# rev_B.net
KiCad netlist of a schematic drawn in EAGLE
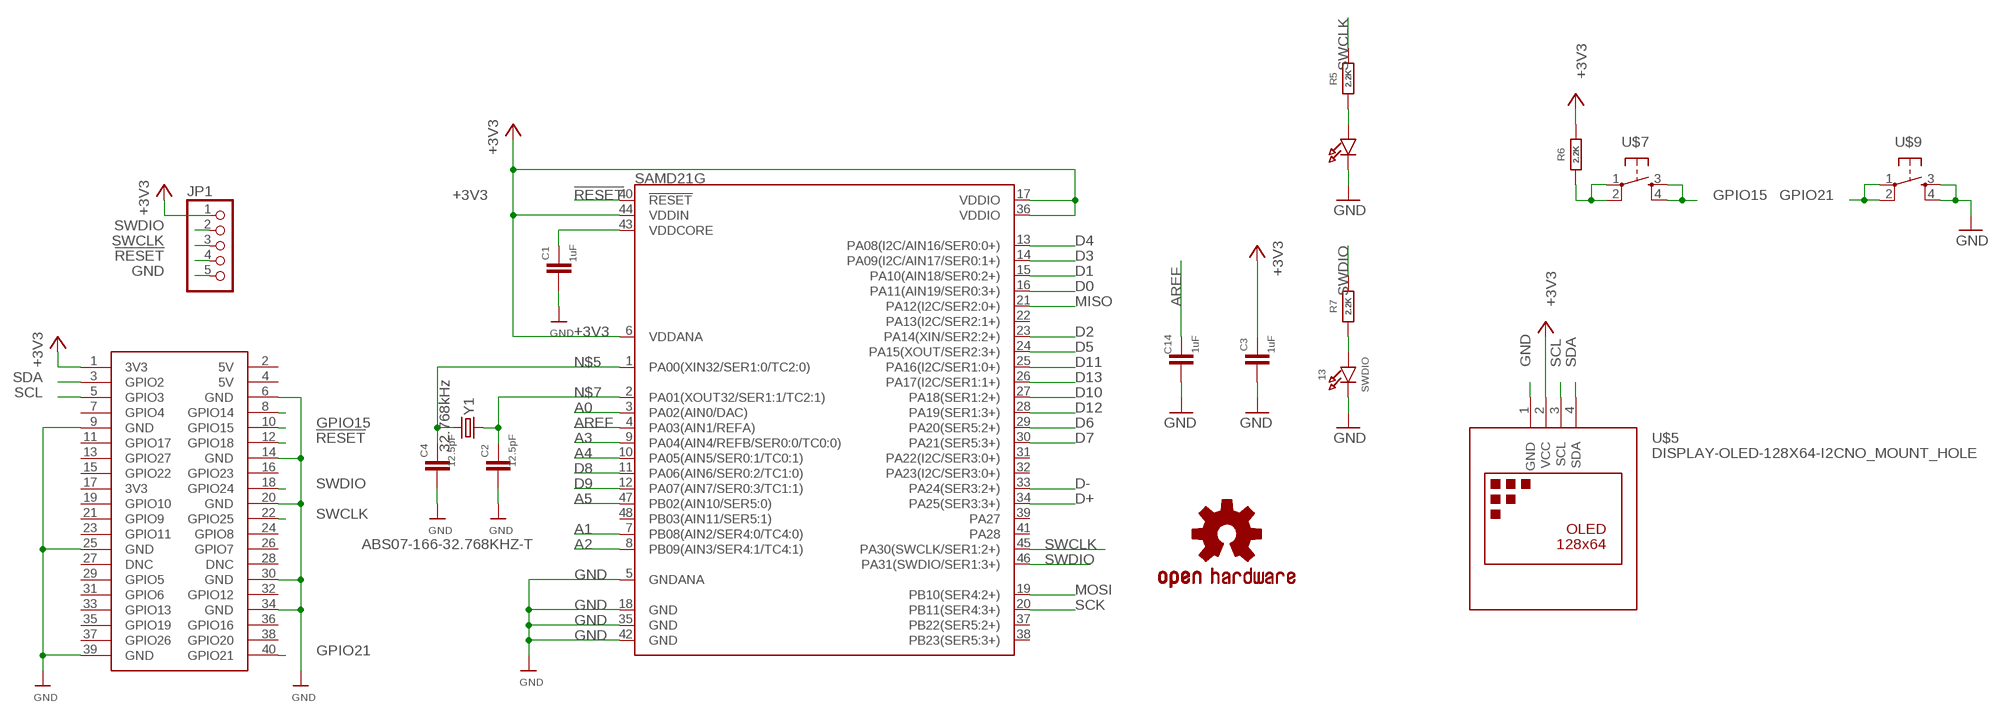
[diagram p0: schematic, sheet 1]

(export (version "E")
  (design (tool "Eeschema 10.0.6"))
  (components
    (comp (ref "5")
      (value "SWCLK")
      (footprint "eagle-import:CHIPLED_0805_NOOUTLINE")
      (libsource (lib "eagle-import") (part "LED0805_NOOUTLINE"))
    )
    (comp (ref "13")
      (value "SWDIO")
      (footprint "eagle-import:CHIPLED_0805_NOOUTLINE")
      (libsource (lib "eagle-import") (part "LED0805_NOOUTLINE"))
    )
    (comp (ref "C1")
      (value "1uF")
      (footprint "eagle-import:C0805")
      (libsource (lib "eagle-import") (part "C-EUC0805"))
    )
    (comp (ref "C2")
      (value "12.5pF")
      (footprint "eagle-import:C0805")
      (libsource (lib "eagle-import") (part "C-EUC0805"))
    )
    (comp (ref "C3")
      (value "1uF")
      (footprint "eagle-import:C0805")
      (libsource (lib "eagle-import") (part "C-EUC0805"))
    )
    (comp (ref "C4")
      (value "12.5pF")
      (footprint "eagle-import:C0805")
      (libsource (lib "eagle-import") (part "C-EUC0805"))
    )
    (comp (ref "C14")
      (value "1uF")
      (footprint "eagle-import:C0805")
      (libsource (lib "eagle-import") (part "C-EUC0805"))
    )
    (comp (ref "JP1")
      (value "PINHD-1X5")
      (footprint "eagle-import:1X05")
      (libsource (lib "eagle-import") (part "PINHD-1X5"))
    )
    (comp (ref "LOGO1")
      (value "OSHW-LOGOS")
      (footprint "eagle-import:OSHW-LOGO-S")
      (libsource (lib "eagle-import") (part "OSHW-LOGOS"))
    )
    (comp (ref "R5")
      (value "2.2K")
      (footprint "eagle-import:R0805")
      (libsource (lib "eagle-import") (part "R-EU_R0805"))
    )
    (comp (ref "R6")
      (value "2.2K")
      (footprint "eagle-import:R0805")
      (libsource (lib "eagle-import") (part "R-EU_R0805"))
    )
    (comp (ref "R7")
      (value "2.2K")
      (footprint "eagle-import:R0805")
      (libsource (lib "eagle-import") (part "R-EU_R0805"))
    )
    (comp (ref "SAMD21G")
      (value "ATSAMD21G-A")
      (footprint "eagle-import:TQFP-48")
      (libsource (lib "eagle-import") (part "ATSAMD21G-A"))
    )
    (comp (ref "U$1")
      (value "RASPBERRY_PI_ZERO")
      (footprint "eagle-import:RASPBERRY_PI_ZERO")
      (libsource (lib "eagle-import") (part "RASPBERRY_PI_ZERO"))
    )
    (comp (ref "U$5")
      (value "DISPLAY-OLED-128X64-I2CNO_MOUNT_HOLE")
      (footprint "eagle-import:DISPLAY-OLED-128X64-I2C")
      (libsource (lib "eagle-import") (part "DISPLAY-OLED-128X64-I2CNO_MOUNT_HOLE"))
    )
    (comp (ref "U$7")
      (value "TACTILE_SWITCH_LONG_THT_")
      (footprint "eagle-import:TACTILE_SWICTH_THT")
      (libsource (lib "eagle-import") (part "TACTILE_SWITCH_LONG_THT_"))
    )
    (comp (ref "U$9")
      (value "TACTILE_SWITCH_LONG_THT_")
      (footprint "eagle-import:TACTILE_SWICTH_THT")
      (libsource (lib "eagle-import") (part "TACTILE_SWITCH_LONG_THT_"))
    )
    (comp (ref "Y1")
      (value "32.768kHz")
      (footprint "eagle-import:CRYSTAL-SMD-3.2X1.5MM")
      (libsource (lib "eagle-import") (part "CRYSTAL3.2X1.5MM"))
    )
  )
  (nets
    (net (code "1") (name "+3V3") (class "Default")
      (node (ref "C3") (pin "1") (pinfunction "1_1") (pintype "passive"))
      (node (ref "JP1") (pin "1") (pinfunction "1_1") (pintype "passive"))
      (node (ref "R6") (pin "1") (pinfunction "1_1") (pintype "passive"))
      (node (ref "SAMD21G") (pin "17") (pinfunction "VDDIO_17") (pintype "bidirectional"))
      (node (ref "SAMD21G") (pin "36") (pinfunction "VDDIO_36") (pintype "bidirectional"))
      (node (ref "SAMD21G") (pin "44") (pinfunction "VDDIN_44") (pintype "bidirectional"))
      (node (ref "SAMD21G") (pin "6") (pinfunction "VDDANA_6") (pintype "bidirectional"))
      (node (ref "U$1") (pin "1") (pinfunction "3V3_1") (pintype "bidirectional"))
      (node (ref "U$5") (pin "2") (pinfunction "VCC_2") (pintype "power_in"))
    )
    (net (code "2") (name "/A0") (class "Default")
      (node (ref "SAMD21G") (pin "3") (pinfunction "PA02(AIN0/DAC)_3") (pintype "bidirectional"))
    )
    (net (code "3") (name "/A1") (class "Default")
      (node (ref "SAMD21G") (pin "7") (pinfunction "PB08(AIN2/SER4:0/TC4:0)_7") (pintype "bidirectional"))
    )
    (net (code "4") (name "/A2") (class "Default")
      (node (ref "SAMD21G") (pin "8") (pinfunction "PB09(AIN3/SER4:1/TC4:1)_8") (pintype "bidirectional"))
    )
    (net (code "5") (name "/A3") (class "Default")
      (node (ref "SAMD21G") (pin "9") (pinfunction "PA04(AIN4/REFB/SER0:0/TC0:0)_9") (pintype "bidirectional"))
    )
    (net (code "6") (name "/A4") (class "Default")
      (node (ref "SAMD21G") (pin "10") (pinfunction "PA05(AIN5/SER0:1/TC0:1)_10") (pintype "bidirectional"))
    )
    (net (code "7") (name "/A5") (class "Default")
      (node (ref "SAMD21G") (pin "47") (pinfunction "PB02(AIN10/SER5:0)_47") (pintype "bidirectional"))
    )
    (net (code "8") (name "/AREF") (class "Default")
      (node (ref "C14") (pin "1") (pinfunction "1_1") (pintype "passive"))
      (node (ref "SAMD21G") (pin "4") (pinfunction "PA03(AIN1/REFA)_4") (pintype "bidirectional"))
    )
    (net (code "9") (name "/D+") (class "Default")
      (node (ref "SAMD21G") (pin "34") (pinfunction "PA25(SER3:3+)_34") (pintype "bidirectional"))
    )
    (net (code "10") (name "/D-") (class "Default")
      (node (ref "SAMD21G") (pin "33") (pinfunction "PA24(SER3:2+)_33") (pintype "bidirectional"))
    )
    (net (code "11") (name "/D0") (class "Default")
      (node (ref "SAMD21G") (pin "16") (pinfunction "PA11(AIN19/SER0:3+)_16") (pintype "bidirectional"))
    )
    (net (code "12") (name "/D1") (class "Default")
      (node (ref "SAMD21G") (pin "15") (pinfunction "PA10(AIN18/SER0:2+)_15") (pintype "bidirectional"))
    )
    (net (code "13") (name "/D2") (class "Default")
      (node (ref "SAMD21G") (pin "23") (pinfunction "PA14(XIN/SER2:2+)_23") (pintype "bidirectional"))
    )
    (net (code "14") (name "/D3") (class "Default")
      (node (ref "SAMD21G") (pin "14") (pinfunction "PA09(I2C/AIN17/SER0:1+)_14") (pintype "bidirectional"))
    )
    (net (code "15") (name "/D4") (class "Default")
      (node (ref "SAMD21G") (pin "13") (pinfunction "PA08(I2C/AIN16/SER0:0+)_13") (pintype "bidirectional"))
    )
    (net (code "16") (name "/D5") (class "Default")
      (node (ref "SAMD21G") (pin "24") (pinfunction "PA15(XOUT/SER2:3+)_24") (pintype "bidirectional"))
    )
    (net (code "17") (name "/D6") (class "Default")
      (node (ref "SAMD21G") (pin "29") (pinfunction "PA20(SER5:2+)_29") (pintype "bidirectional"))
    )
    (net (code "18") (name "/D7") (class "Default")
      (node (ref "SAMD21G") (pin "30") (pinfunction "PA21(SER5:3+)_30") (pintype "bidirectional"))
    )
    (net (code "19") (name "/D8") (class "Default")
      (node (ref "SAMD21G") (pin "11") (pinfunction "PA06(AIN6/SER0:2/TC1:0)_11") (pintype "bidirectional"))
    )
    (net (code "20") (name "/D9") (class "Default")
      (node (ref "SAMD21G") (pin "12") (pinfunction "PA07(AIN7/SER0:3/TC1:1)_12") (pintype "bidirectional"))
    )
    (net (code "21") (name "/D10") (class "Default")
      (node (ref "SAMD21G") (pin "27") (pinfunction "PA18(SER1:2+)_27") (pintype "bidirectional"))
    )
    (net (code "22") (name "/D11") (class "Default")
      (node (ref "SAMD21G") (pin "25") (pinfunction "PA16(I2C/SER1:0+)_25") (pintype "bidirectional"))
    )
    (net (code "23") (name "/D12") (class "Default")
      (node (ref "SAMD21G") (pin "28") (pinfunction "PA19(SER1:3+)_28") (pintype "bidirectional"))
    )
    (net (code "24") (name "/D13") (class "Default")
      (node (ref "SAMD21G") (pin "26") (pinfunction "PA17(I2C/SER1:1+)_26") (pintype "bidirectional"))
    )
    (net (code "25") (name "/GPIO15") (class "Default")
      (node (ref "U$1") (pin "10") (pinfunction "GPIO15_10") (pintype "bidirectional"))
      (node (ref "U$7") (pin "3") (pinfunction "3_3") (pintype "passive"))
      (node (ref "U$7") (pin "4") (pinfunction "4_4") (pintype "passive"))
    )
    (net (code "26") (name "/GPIO21") (class "Default")
      (node (ref "U$1") (pin "40") (pinfunction "GPIO21_40") (pintype "bidirectional"))
      (node (ref "U$9") (pin "1") (pinfunction "1_1") (pintype "passive"))
      (node (ref "U$9") (pin "2") (pinfunction "2_2") (pintype "passive"))
    )
    (net (code "27") (name "/MISO") (class "Default")
      (node (ref "SAMD21G") (pin "21") (pinfunction "PA12(I2C/SER2:0+)_21") (pintype "bidirectional"))
    )
    (net (code "28") (name "/MOSI") (class "Default")
      (node (ref "SAMD21G") (pin "19") (pinfunction "PB10(SER4:2+)_19") (pintype "bidirectional"))
    )
    (net (code "29") (name "/N$5") (class "Default")
      (node (ref "C4") (pin "1") (pinfunction "1_1") (pintype "passive"))
      (node (ref "SAMD21G") (pin "1") (pinfunction "PA00(XIN32/SER1:0/TC2:0)_1") (pintype "bidirectional"))
      (node (ref "Y1") (pin "P$2") (pinfunction "2_P$2") (pintype "passive"))
    )
    (net (code "30") (name "/N$7") (class "Default")
      (node (ref "C2") (pin "1") (pinfunction "1_1") (pintype "passive"))
      (node (ref "SAMD21G") (pin "2") (pinfunction "PA01(XOUT32/SER1:1/TC2:1)_2") (pintype "bidirectional"))
      (node (ref "Y1") (pin "P$1") (pinfunction "1_P$1") (pintype "passive"))
    )
    (net (code "31") (name "/SCK") (class "Default")
      (node (ref "SAMD21G") (pin "20") (pinfunction "PB11(SER4:3+)_20") (pintype "bidirectional"))
    )
    (net (code "32") (name "/SCL") (class "Default")
      (node (ref "U$1") (pin "5") (pinfunction "GPIO3_5") (pintype "bidirectional"))
      (node (ref "U$5") (pin "3") (pinfunction "SCL_3") (pintype "bidirectional"))
    )
    (net (code "33") (name "/SDA") (class "Default")
      (node (ref "U$1") (pin "3") (pinfunction "GPIO2_3") (pintype "bidirectional"))
      (node (ref "U$5") (pin "4") (pinfunction "SDA_4") (pintype "bidirectional"))
    )
    (net (code "34") (name "/SWCLK") (class "Default")
      (node (ref "JP1") (pin "3") (pinfunction "3_3") (pintype "passive"))
      (node (ref "R5") (pin "1") (pinfunction "1_1") (pintype "passive"))
      (node (ref "SAMD21G") (pin "45") (pinfunction "PA30(SWCLK/SER1:2+)_45") (pintype "bidirectional"))
      (node (ref "U$1") (pin "22") (pinfunction "GPIO25_22") (pintype "bidirectional"))
    )
    (net (code "35") (name "/SWDIO") (class "Default")
      (node (ref "JP1") (pin "2") (pinfunction "2_2") (pintype "passive"))
      (node (ref "R7") (pin "1") (pinfunction "1_1") (pintype "passive"))
      (node (ref "SAMD21G") (pin "46") (pinfunction "PA31(SWDIO/SER1:3+)_46") (pintype "bidirectional"))
      (node (ref "U$1") (pin "18") (pinfunction "GPIO24_18") (pintype "bidirectional"))
    )
    (net (code "36") (name "/~{RESET}") (class "Default")
      (node (ref "JP1") (pin "4") (pinfunction "4_4") (pintype "passive"))
      (node (ref "SAMD21G") (pin "40") (pinfunction "~{RESET}_40") (pintype "bidirectional"))
      (node (ref "U$1") (pin "12") (pinfunction "GPIO18_12") (pintype "bidirectional"))
    )
    (net (code "37") (name "GND") (class "Default")
      (node (ref "13") (pin "C") (pinfunction "C_C") (pintype "passive"))
      (node (ref "5") (pin "C") (pinfunction "C_C") (pintype "passive"))
      (node (ref "C1") (pin "2") (pinfunction "2_2") (pintype "passive"))
      (node (ref "C14") (pin "2") (pinfunction "2_2") (pintype "passive"))
      (node (ref "C2") (pin "2") (pinfunction "2_2") (pintype "passive"))
      (node (ref "C3") (pin "2") (pinfunction "2_2") (pintype "passive"))
      (node (ref "C4") (pin "2") (pinfunction "2_2") (pintype "passive"))
      (node (ref "JP1") (pin "5") (pinfunction "5_5") (pintype "passive"))
      (node (ref "SAMD21G") (pin "18") (pinfunction "GND_18") (pintype "bidirectional"))
      (node (ref "SAMD21G") (pin "35") (pinfunction "GND_35") (pintype "bidirectional"))
      (node (ref "SAMD21G") (pin "42") (pinfunction "GND_42") (pintype "bidirectional"))
      (node (ref "SAMD21G") (pin "5") (pinfunction "GNDANA_5") (pintype "bidirectional"))
      (node (ref "U$1") (pin "14") (pinfunction "GND_14") (pintype "bidirectional"))
      (node (ref "U$1") (pin "20") (pinfunction "GND_20") (pintype "bidirectional"))
      (node (ref "U$1") (pin "25") (pinfunction "GND_25") (pintype "bidirectional"))
      (node (ref "U$1") (pin "30") (pinfunction "GND_30") (pintype "bidirectional"))
      (node (ref "U$1") (pin "34") (pinfunction "GND_34") (pintype "bidirectional"))
      (node (ref "U$1") (pin "39") (pinfunction "GND_39") (pintype "bidirectional"))
      (node (ref "U$1") (pin "6") (pinfunction "GND_6") (pintype "bidirectional"))
      (node (ref "U$1") (pin "9") (pinfunction "GND_9") (pintype "bidirectional"))
      (node (ref "U$5") (pin "1") (pinfunction "GND_1") (pintype "power_in"))
      (node (ref "U$9") (pin "3") (pinfunction "3_3") (pintype "passive"))
      (node (ref "U$9") (pin "4") (pinfunction "4_4") (pintype "passive"))
    )
    (net (code "38") (name "Net-(5-PadA)") (class "Default")
      (node (ref "5") (pin "A") (pinfunction "A_A") (pintype "passive"))
      (node (ref "R5") (pin "2") (pinfunction "2_2") (pintype "passive"))
    )
    (net (code "39") (name "Net-(13-PadA)") (class "Default")
      (node (ref "13") (pin "A") (pinfunction "A_A") (pintype "passive"))
      (node (ref "R7") (pin "2") (pinfunction "2_2") (pintype "passive"))
    )
    (net (code "40") (name "Net-(R6-Pad2)") (class "Default")
      (node (ref "R6") (pin "2") (pinfunction "2_2") (pintype "passive"))
      (node (ref "U$7") (pin "1") (pinfunction "1_1") (pintype "passive"))
      (node (ref "U$7") (pin "2") (pinfunction "2_2") (pintype "passive"))
    )
    (net (code "41") (name "Net-(SAMD21G-VDDCORE)") (class "Default")
      (node (ref "C1") (pin "1") (pinfunction "1_1") (pintype "passive"))
      (node (ref "SAMD21G") (pin "43") (pinfunction "VDDCORE_43") (pintype "bidirectional"))
    )
    (net (code "42") (name "unconnected-(SAMD21G-PA13(I2C{slash}SER2:1+)-Pad22)") (class "Default")
      (node (ref "SAMD21G") (pin "22") (pinfunction "PA13(I2C/SER2:1+)_22") (pintype "bidirectional"))
    )
    (net (code "43") (name "unconnected-(SAMD21G-PA22(I2C{slash}SER3:0+)-Pad31)") (class "Default")
      (node (ref "SAMD21G") (pin "31") (pinfunction "PA22(I2C/SER3:0+)_31") (pintype "bidirectional"))
    )
    (net (code "44") (name "unconnected-(SAMD21G-PA23(I2C{slash}SER3:0+)-Pad32)") (class "Default")
      (node (ref "SAMD21G") (pin "32") (pinfunction "PA23(I2C/SER3:0+)_32") (pintype "bidirectional"))
    )
    (net (code "45") (name "unconnected-(SAMD21G-PA27-Pad39)") (class "Default")
      (node (ref "SAMD21G") (pin "39") (pinfunction "PA27_39") (pintype "bidirectional"))
    )
    (net (code "46") (name "unconnected-(SAMD21G-PA28-Pad41)") (class "Default")
      (node (ref "SAMD21G") (pin "41") (pinfunction "PA28_41") (pintype "bidirectional"))
    )
    (net (code "47") (name "unconnected-(SAMD21G-PB03(AIN11{slash}SER5:1)-Pad48)") (class "Default")
      (node (ref "SAMD21G") (pin "48") (pinfunction "PB03(AIN11/SER5:1)_48") (pintype "bidirectional"))
    )
    (net (code "48") (name "unconnected-(SAMD21G-PB22(SER5:2+)-Pad37)") (class "Default")
      (node (ref "SAMD21G") (pin "37") (pinfunction "PB22(SER5:2+)_37") (pintype "bidirectional"))
    )
    (net (code "49") (name "unconnected-(SAMD21G-PB23(SER5:3+)-Pad38)") (class "Default")
      (node (ref "SAMD21G") (pin "38") (pinfunction "PB23(SER5:3+)_38") (pintype "bidirectional"))
    )
    (net (code "50") (name "unconnected-(U$1-3V3-Pad17)") (class "Default")
      (node (ref "U$1") (pin "17") (pinfunction "3V3_17") (pintype "bidirectional"))
    )
    (net (code "51") (name "unconnected-(U$1-5V-Pad2)") (class "Default")
      (node (ref "U$1") (pin "2") (pinfunction "5V_2") (pintype "bidirectional"))
    )
    (net (code "52") (name "unconnected-(U$1-5V-Pad4)") (class "Default")
      (node (ref "U$1") (pin "4") (pinfunction "5V_4") (pintype "bidirectional"))
    )
    (net (code "53") (name "unconnected-(U$1-DNC-Pad27)") (class "Default")
      (node (ref "U$1") (pin "27") (pinfunction "DNC_27") (pintype "bidirectional"))
    )
    (net (code "54") (name "unconnected-(U$1-DNC-Pad28)") (class "Default")
      (node (ref "U$1") (pin "28") (pinfunction "DNC_28") (pintype "bidirectional"))
    )
    (net (code "55") (name "unconnected-(U$1-GPIO4-Pad7)") (class "Default")
      (node (ref "U$1") (pin "7") (pinfunction "GPIO4_7") (pintype "bidirectional"))
    )
    (net (code "56") (name "unconnected-(U$1-GPIO5-Pad29)") (class "Default")
      (node (ref "U$1") (pin "29") (pinfunction "GPIO5_29") (pintype "bidirectional"))
    )
    (net (code "57") (name "unconnected-(U$1-GPIO6-Pad31)") (class "Default")
      (node (ref "U$1") (pin "31") (pinfunction "GPIO6_31") (pintype "bidirectional"))
    )
    (net (code "58") (name "unconnected-(U$1-GPIO7-Pad26)") (class "Default")
      (node (ref "U$1") (pin "26") (pinfunction "GPIO7_26") (pintype "bidirectional"))
    )
    (net (code "59") (name "unconnected-(U$1-GPIO8-Pad24)") (class "Default")
      (node (ref "U$1") (pin "24") (pinfunction "GPIO8_24") (pintype "bidirectional"))
    )
    (net (code "60") (name "unconnected-(U$1-GPIO9-Pad21)") (class "Default")
      (node (ref "U$1") (pin "21") (pinfunction "GPIO9_21") (pintype "bidirectional"))
    )
    (net (code "61") (name "unconnected-(U$1-GPIO10-Pad19)") (class "Default")
      (node (ref "U$1") (pin "19") (pinfunction "GPIO10_19") (pintype "bidirectional"))
    )
    (net (code "62") (name "unconnected-(U$1-GPIO11-Pad23)") (class "Default")
      (node (ref "U$1") (pin "23") (pinfunction "GPIO11_23") (pintype "bidirectional"))
    )
    (net (code "63") (name "unconnected-(U$1-GPIO12-Pad32)") (class "Default")
      (node (ref "U$1") (pin "32") (pinfunction "GPIO12_32") (pintype "bidirectional"))
    )
    (net (code "64") (name "unconnected-(U$1-GPIO13-Pad33)") (class "Default")
      (node (ref "U$1") (pin "33") (pinfunction "GPIO13_33") (pintype "bidirectional"))
    )
    (net (code "65") (name "unconnected-(U$1-GPIO14-Pad8)") (class "Default")
      (node (ref "U$1") (pin "8") (pinfunction "GPIO14_8") (pintype "bidirectional"))
    )
    (net (code "66") (name "unconnected-(U$1-GPIO16-Pad36)") (class "Default")
      (node (ref "U$1") (pin "36") (pinfunction "GPIO16_36") (pintype "bidirectional"))
    )
    (net (code "67") (name "unconnected-(U$1-GPIO17-Pad11)") (class "Default")
      (node (ref "U$1") (pin "11") (pinfunction "GPIO17_11") (pintype "bidirectional"))
    )
    (net (code "68") (name "unconnected-(U$1-GPIO19-Pad35)") (class "Default")
      (node (ref "U$1") (pin "35") (pinfunction "GPIO19_35") (pintype "bidirectional"))
    )
    (net (code "69") (name "unconnected-(U$1-GPIO20-Pad38)") (class "Default")
      (node (ref "U$1") (pin "38") (pinfunction "GPIO20_38") (pintype "bidirectional"))
    )
    (net (code "70") (name "unconnected-(U$1-GPIO22-Pad15)") (class "Default")
      (node (ref "U$1") (pin "15") (pinfunction "GPIO22_15") (pintype "bidirectional"))
    )
    (net (code "71") (name "unconnected-(U$1-GPIO23-Pad16)") (class "Default")
      (node (ref "U$1") (pin "16") (pinfunction "GPIO23_16") (pintype "bidirectional"))
    )
    (net (code "72") (name "unconnected-(U$1-GPIO26-Pad37)") (class "Default")
      (node (ref "U$1") (pin "37") (pinfunction "GPIO26_37") (pintype "bidirectional"))
    )
    (net (code "73") (name "unconnected-(U$1-GPIO27-Pad13)") (class "Default")
      (node (ref "U$1") (pin "13") (pinfunction "GPIO27_13") (pintype "bidirectional"))
    )
  )
)
